# grbl_shield_hector.net
KiCad netlist of a schematic drawn in EAGLE
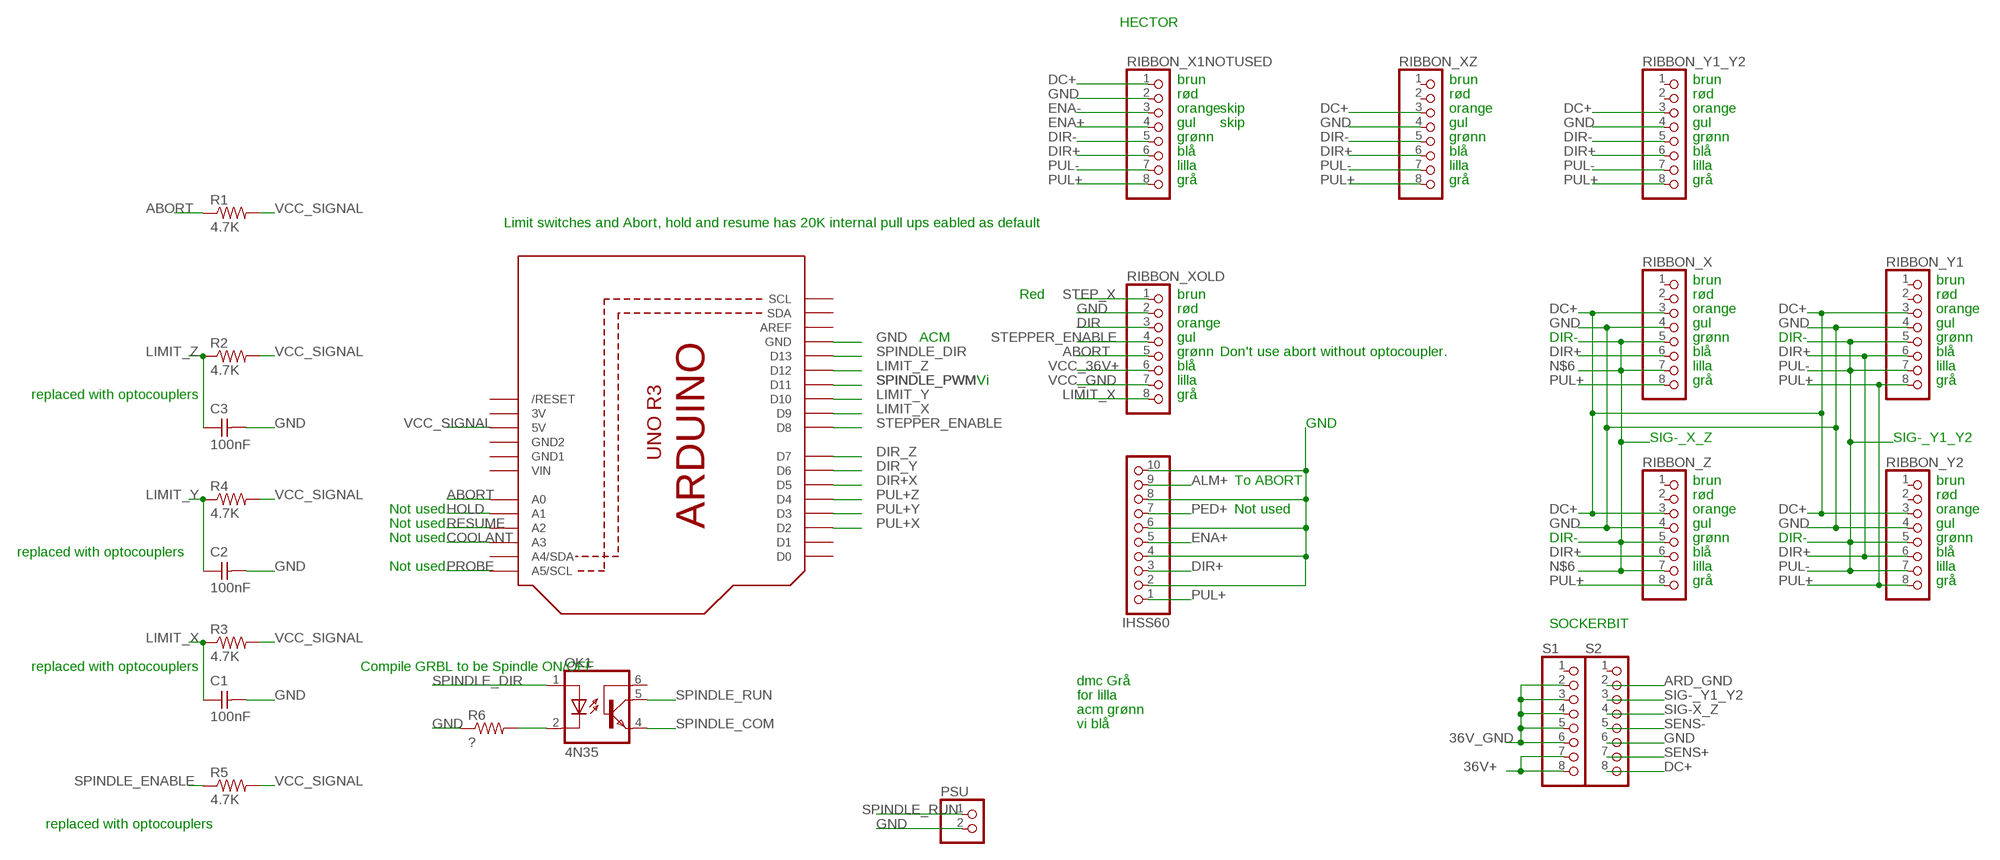
[diagram p0: schematic, sheet 1]

(export (version "E")
  (design (tool "Eeschema 10.0.6"))
  (components
    (comp (ref "C1")
      (value "100nF")
      (footprint "eagle-import:C1206FAB")
      (libsource (lib "eagle-import") (part "CAP-UNPOLARIZEDFAB"))
    )
    (comp (ref "C2")
      (value "100nF")
      (footprint "eagle-import:C1206FAB")
      (libsource (lib "eagle-import") (part "CAP-UNPOLARIZEDFAB"))
    )
    (comp (ref "C3")
      (value "100nF")
      (footprint "eagle-import:C1206FAB")
      (libsource (lib "eagle-import") (part "CAP-UNPOLARIZEDFAB"))
    )
    (comp (ref "IHSS60")
      (value "PINHD-1X10")
      (footprint "eagle-import:1X10")
      (libsource (lib "eagle-import") (part "PINHD-1X10"))
    )
    (comp (ref "OK1")
      (value "4N35")
      (footprint "eagle-import:DIL06")
      (libsource (lib "eagle-import") (part "4N35"))
    )
    (comp (ref "PSU")
      (value "PINHD-1X2")
      (footprint "eagle-import:1X02")
      (libsource (lib "eagle-import") (part "PINHD-1X2"))
    )
    (comp (ref "Q1")
      (value "ARDUINOR3-NOIOREF-NOTEXT")
      (footprint "eagle-import:ARDUINOR3-NOTEXT-NOIOREF")
      (libsource (lib "eagle-import") (part "ARDUINOR3-NOIOREF-NOTEXT"))
    )
    (comp (ref "R1")
      (value "4.7K")
      (footprint "eagle-import:R1206FAB")
      (libsource (lib "eagle-import") (part "RES-US1206FAB"))
    )
    (comp (ref "R2")
      (value "4.7K")
      (footprint "eagle-import:R1206FAB")
      (libsource (lib "eagle-import") (part "RES-US1206FAB"))
    )
    (comp (ref "R3")
      (value "4.7K")
      (footprint "eagle-import:R1206FAB")
      (libsource (lib "eagle-import") (part "RES-US1206FAB"))
    )
    (comp (ref "R4")
      (value "4.7K")
      (footprint "eagle-import:R1206FAB")
      (libsource (lib "eagle-import") (part "RES-US1206FAB"))
    )
    (comp (ref "R5")
      (value "4.7K")
      (footprint "eagle-import:R1206FAB")
      (libsource (lib "eagle-import") (part "RES-US1206FAB"))
    )
    (comp (ref "R6")
      (value "?")
      (footprint "eagle-import:R1206FAB")
      (libsource (lib "eagle-import") (part "RES-US1206FAB"))
    )
    (comp (ref "RIBBON_X")
      (value "PINHD-1X8")
      (footprint "eagle-import:1X08")
      (libsource (lib "eagle-import") (part "PINHD-1X8"))
    )
    (comp (ref "RIBBON_X1NOTUSED")
      (value "PINHD-1X8")
      (footprint "eagle-import:1X08")
      (libsource (lib "eagle-import") (part "PINHD-1X8"))
    )
    (comp (ref "RIBBON_XOLD")
      (value "PINHD-1X8")
      (footprint "eagle-import:1X08")
      (libsource (lib "eagle-import") (part "PINHD-1X8"))
    )
    (comp (ref "RIBBON_XZ")
      (value "PINHD-1X8")
      (footprint "eagle-import:1X08")
      (libsource (lib "eagle-import") (part "PINHD-1X8"))
    )
    (comp (ref "RIBBON_Y1")
      (value "PINHD-1X8")
      (footprint "eagle-import:1X08")
      (libsource (lib "eagle-import") (part "PINHD-1X8"))
    )
    (comp (ref "RIBBON_Y1_Y2")
      (value "PINHD-1X8")
      (footprint "eagle-import:1X08")
      (libsource (lib "eagle-import") (part "PINHD-1X8"))
    )
    (comp (ref "RIBBON_Y2")
      (value "PINHD-1X8")
      (footprint "eagle-import:1X08")
      (libsource (lib "eagle-import") (part "PINHD-1X8"))
    )
    (comp (ref "RIBBON_Z")
      (value "PINHD-1X8")
      (footprint "eagle-import:1X08")
      (libsource (lib "eagle-import") (part "PINHD-1X8"))
    )
    (comp (ref "S1")
      (value "PINHD-1X8")
      (footprint "eagle-import:1X08")
      (libsource (lib "eagle-import") (part "PINHD-1X8"))
    )
    (comp (ref "S2")
      (value "PINHD-1X8")
      (footprint "eagle-import:1X08")
      (libsource (lib "eagle-import") (part "PINHD-1X8"))
    )
  )
  (nets
    (net (code "1") (name "/3V") (class "Default")
      (node (ref "Q1") (pin "3V") (pinfunction "3V_3V") (pintype "power_in"))
    )
    (net (code "2") (name "/36V+") (class "Default")
      (node (ref "S1") (pin "7") (pinfunction "7_7") (pintype "passive"))
      (node (ref "S1") (pin "8") (pinfunction "8_8") (pintype "passive"))
    )
    (net (code "3") (name "/36V_GND") (class "Default")
      (node (ref "S1") (pin "2") (pinfunction "2_2") (pintype "passive"))
      (node (ref "S1") (pin "3") (pinfunction "3_3") (pintype "passive"))
      (node (ref "S1") (pin "4") (pinfunction "4_4") (pintype "passive"))
      (node (ref "S1") (pin "5") (pinfunction "5_5") (pintype "passive"))
      (node (ref "S1") (pin "6") (pinfunction "6_6") (pintype "passive"))
    )
    (net (code "4") (name "/ABORT") (class "Default")
      (node (ref "Q1") (pin "A0") (pinfunction "A0_A0") (pintype "bidirectional"))
      (node (ref "R1") (pin "1") (pinfunction "1_1") (pintype "passive"))
      (node (ref "RIBBON_XOLD") (pin "5") (pinfunction "5_5") (pintype "passive"))
    )
    (net (code "5") (name "/ALM+") (class "Default")
      (node (ref "IHSS60") (pin "9") (pinfunction "9_9") (pintype "passive"))
    )
    (net (code "6") (name "/ARD_GND") (class "Default")
      (node (ref "S2") (pin "2") (pinfunction "2_2") (pintype "passive"))
    )
    (net (code "7") (name "/COOLANT") (class "Default")
      (node (ref "Q1") (pin "A3") (pinfunction "A3_A3") (pintype "bidirectional"))
    )
    (net (code "8") (name "/DC+") (class "Default")
      (node (ref "RIBBON_X") (pin "3") (pinfunction "3_3") (pintype "passive"))
      (node (ref "RIBBON_X1NOTUSED") (pin "1") (pinfunction "1_1") (pintype "passive"))
      (node (ref "RIBBON_XZ") (pin "3") (pinfunction "3_3") (pintype "passive"))
      (node (ref "RIBBON_Y1") (pin "3") (pinfunction "3_3") (pintype "passive"))
      (node (ref "RIBBON_Y1_Y2") (pin "3") (pinfunction "3_3") (pintype "passive"))
      (node (ref "RIBBON_Y2") (pin "3") (pinfunction "3_3") (pintype "passive"))
      (node (ref "RIBBON_Z") (pin "3") (pinfunction "3_3") (pintype "passive"))
      (node (ref "S2") (pin "8") (pinfunction "8_8") (pintype "passive"))
    )
    (net (code "9") (name "/DIR") (class "Default")
      (node (ref "RIBBON_XOLD") (pin "3") (pinfunction "3_3") (pintype "passive"))
    )
    (net (code "10") (name "/DIR+") (class "Default")
      (node (ref "IHSS60") (pin "3") (pinfunction "3_3") (pintype "passive"))
      (node (ref "RIBBON_X") (pin "6") (pinfunction "6_6") (pintype "passive"))
      (node (ref "RIBBON_X1NOTUSED") (pin "6") (pinfunction "6_6") (pintype "passive"))
      (node (ref "RIBBON_XZ") (pin "6") (pinfunction "6_6") (pintype "passive"))
      (node (ref "RIBBON_Y1") (pin "6") (pinfunction "6_6") (pintype "passive"))
      (node (ref "RIBBON_Y1_Y2") (pin "6") (pinfunction "6_6") (pintype "passive"))
      (node (ref "RIBBON_Y2") (pin "6") (pinfunction "6_6") (pintype "passive"))
      (node (ref "RIBBON_Z") (pin "6") (pinfunction "6_6") (pintype "passive"))
    )
    (net (code "11") (name "/DIR+X") (class "Default")
      (node (ref "Q1") (pin "D5") (pinfunction "D5_D5") (pintype "bidirectional"))
    )
    (net (code "12") (name "/DIR-") (class "Default")
      (node (ref "RIBBON_X1NOTUSED") (pin "5") (pinfunction "5_5") (pintype "passive"))
      (node (ref "RIBBON_XZ") (pin "5") (pinfunction "5_5") (pintype "passive"))
      (node (ref "RIBBON_Y1_Y2") (pin "5") (pinfunction "5_5") (pintype "passive"))
    )
    (net (code "13") (name "/DIR_Y") (class "Default")
      (node (ref "Q1") (pin "D6") (pinfunction "D6_D6") (pintype "bidirectional"))
    )
    (net (code "14") (name "/DIR_Z") (class "Default")
      (node (ref "Q1") (pin "D7") (pinfunction "D7_D7") (pintype "bidirectional"))
    )
    (net (code "15") (name "/ENA+") (class "Default")
      (node (ref "IHSS60") (pin "5") (pinfunction "5_5") (pintype "passive"))
      (node (ref "RIBBON_X1NOTUSED") (pin "4") (pinfunction "4_4") (pintype "passive"))
    )
    (net (code "16") (name "/ENA-") (class "Default")
      (node (ref "RIBBON_X1NOTUSED") (pin "3") (pinfunction "3_3") (pintype "passive"))
    )
    (net (code "17") (name "/GND") (class "Default")
      (node (ref "C1") (pin "2") (pinfunction "2_2") (pintype "passive"))
      (node (ref "C2") (pin "2") (pinfunction "2_2") (pintype "passive"))
      (node (ref "C3") (pin "2") (pinfunction "2_2") (pintype "passive"))
      (node (ref "PSU") (pin "2") (pinfunction "2_2") (pintype "passive"))
      (node (ref "Q1") (pin "GND") (pinfunction "GND_GND") (pintype "power_in"))
      (node (ref "R6") (pin "1") (pinfunction "1_1") (pintype "passive"))
      (node (ref "RIBBON_X") (pin "4") (pinfunction "4_4") (pintype "passive"))
      (node (ref "RIBBON_X1NOTUSED") (pin "2") (pinfunction "2_2") (pintype "passive"))
      (node (ref "RIBBON_XOLD") (pin "2") (pinfunction "2_2") (pintype "passive"))
      (node (ref "RIBBON_XZ") (pin "4") (pinfunction "4_4") (pintype "passive"))
      (node (ref "RIBBON_Y1") (pin "4") (pinfunction "4_4") (pintype "passive"))
      (node (ref "RIBBON_Y1_Y2") (pin "4") (pinfunction "4_4") (pintype "passive"))
      (node (ref "RIBBON_Y2") (pin "4") (pinfunction "4_4") (pintype "passive"))
      (node (ref "RIBBON_Z") (pin "4") (pinfunction "4_4") (pintype "passive"))
      (node (ref "S2") (pin "6") (pinfunction "6_6") (pintype "passive"))
    )
    (net (code "18") (name "/GND1") (class "Default")
      (node (ref "Q1") (pin "GND1") (pinfunction "GND1_GND1") (pintype "power_in"))
    )
    (net (code "19") (name "/GND2") (class "Default")
      (node (ref "Q1") (pin "GND2") (pinfunction "GND2_GND2") (pintype "power_in"))
    )
    (net (code "20") (name "/HOLD") (class "Default")
      (node (ref "Q1") (pin "A1") (pinfunction "A1_A1") (pintype "bidirectional"))
    )
    (net (code "21") (name "/LIMIT_X") (class "Default")
      (node (ref "C1") (pin "1") (pinfunction "1_1") (pintype "passive"))
      (node (ref "Q1") (pin "D9") (pinfunction "D9_D9") (pintype "bidirectional"))
      (node (ref "R3") (pin "1") (pinfunction "1_1") (pintype "passive"))
      (node (ref "RIBBON_XOLD") (pin "8") (pinfunction "8_8") (pintype "passive"))
    )
    (net (code "22") (name "/LIMIT_Y") (class "Default")
      (node (ref "C2") (pin "1") (pinfunction "1_1") (pintype "passive"))
      (node (ref "Q1") (pin "D10") (pinfunction "D10_D10") (pintype "bidirectional"))
      (node (ref "R4") (pin "1") (pinfunction "1_1") (pintype "passive"))
    )
    (net (code "23") (name "/LIMIT_Z") (class "Default")
      (node (ref "C3") (pin "1") (pinfunction "1_1") (pintype "passive"))
      (node (ref "Q1") (pin "D12") (pinfunction "D12_D12") (pintype "bidirectional"))
      (node (ref "R2") (pin "1") (pinfunction "1_1") (pintype "passive"))
    )
    (net (code "24") (name "/N$6") (class "Default")
      (node (ref "RIBBON_X") (pin "5") (pinfunction "5_5") (pintype "passive"))
      (node (ref "RIBBON_X") (pin "7") (pinfunction "7_7") (pintype "passive"))
      (node (ref "RIBBON_Z") (pin "5") (pinfunction "5_5") (pintype "passive"))
      (node (ref "RIBBON_Z") (pin "7") (pinfunction "7_7") (pintype "passive"))
    )
    (net (code "25") (name "/PED+") (class "Default")
      (node (ref "IHSS60") (pin "7") (pinfunction "7_7") (pintype "passive"))
    )
    (net (code "26") (name "/PROBE") (class "Default")
      (node (ref "Q1") (pin "A5") (pinfunction "A5/SCL_A5") (pintype "bidirectional"))
    )
    (net (code "27") (name "/PUL+") (class "Default")
      (node (ref "IHSS60") (pin "1") (pinfunction "1_1") (pintype "passive"))
      (node (ref "RIBBON_X") (pin "8") (pinfunction "8_8") (pintype "passive"))
      (node (ref "RIBBON_X1NOTUSED") (pin "8") (pinfunction "8_8") (pintype "passive"))
      (node (ref "RIBBON_XZ") (pin "8") (pinfunction "8_8") (pintype "passive"))
      (node (ref "RIBBON_Y1") (pin "8") (pinfunction "8_8") (pintype "passive"))
      (node (ref "RIBBON_Y1_Y2") (pin "8") (pinfunction "8_8") (pintype "passive"))
      (node (ref "RIBBON_Y2") (pin "8") (pinfunction "8_8") (pintype "passive"))
      (node (ref "RIBBON_Z") (pin "8") (pinfunction "8_8") (pintype "passive"))
    )
    (net (code "28") (name "/PUL+X") (class "Default")
      (node (ref "Q1") (pin "D2") (pinfunction "D2_D2") (pintype "bidirectional"))
    )
    (net (code "29") (name "/PUL+Y") (class "Default")
      (node (ref "Q1") (pin "D3") (pinfunction "D3_D3") (pintype "bidirectional"))
    )
    (net (code "30") (name "/PUL+Z") (class "Default")
      (node (ref "Q1") (pin "D4") (pinfunction "D4_D4") (pintype "bidirectional"))
    )
    (net (code "31") (name "/PUL-") (class "Default")
      (node (ref "RIBBON_X1NOTUSED") (pin "7") (pinfunction "7_7") (pintype "passive"))
      (node (ref "RIBBON_XZ") (pin "7") (pinfunction "7_7") (pintype "passive"))
      (node (ref "RIBBON_Y1") (pin "5") (pinfunction "5_5") (pintype "passive"))
      (node (ref "RIBBON_Y1") (pin "7") (pinfunction "7_7") (pintype "passive"))
      (node (ref "RIBBON_Y1_Y2") (pin "7") (pinfunction "7_7") (pintype "passive"))
      (node (ref "RIBBON_Y2") (pin "5") (pinfunction "5_5") (pintype "passive"))
      (node (ref "RIBBON_Y2") (pin "7") (pinfunction "7_7") (pintype "passive"))
    )
    (net (code "32") (name "/RESUME") (class "Default")
      (node (ref "Q1") (pin "A2") (pinfunction "A2_A2") (pintype "bidirectional"))
    )
    (net (code "33") (name "/SENS+") (class "Default")
      (node (ref "S2") (pin "7") (pinfunction "7_7") (pintype "passive"))
    )
    (net (code "34") (name "/SENS-") (class "Default")
      (node (ref "S2") (pin "5") (pinfunction "5_5") (pintype "passive"))
    )
    (net (code "35") (name "/SIG-X_Z") (class "Default")
      (node (ref "S2") (pin "4") (pinfunction "4_4") (pintype "passive"))
    )
    (net (code "36") (name "/SIG-_Y1_Y2") (class "Default")
      (node (ref "S2") (pin "3") (pinfunction "3_3") (pintype "passive"))
    )
    (net (code "37") (name "/SPINDLE_COM") (class "Default")
      (node (ref "OK1") (pin "4") (pinfunction "EMI_4") (pintype "passive"))
    )
    (net (code "38") (name "/SPINDLE_DIR") (class "Default")
      (node (ref "OK1") (pin "1") (pinfunction "A_1") (pintype "passive"))
      (node (ref "Q1") (pin "D13") (pinfunction "D13_D13") (pintype "bidirectional"))
    )
    (net (code "39") (name "/SPINDLE_ENABLE") (class "Default")
      (node (ref "R5") (pin "1") (pinfunction "1_1") (pintype "passive"))
    )
    (net (code "40") (name "/SPINDLE_PWM") (class "Default")
      (node (ref "Q1") (pin "D11") (pinfunction "D11_D11") (pintype "bidirectional"))
    )
    (net (code "41") (name "/SPINDLE_RUN") (class "Default")
      (node (ref "OK1") (pin "5") (pinfunction "COL_5") (pintype "passive"))
      (node (ref "PSU") (pin "1") (pinfunction "1_1") (pintype "passive"))
    )
    (net (code "42") (name "/STEPPER_ENABLE") (class "Default")
      (node (ref "Q1") (pin "D8") (pinfunction "D8_D8") (pintype "bidirectional"))
      (node (ref "RIBBON_XOLD") (pin "4") (pinfunction "4_4") (pintype "passive"))
    )
    (net (code "43") (name "/STEP_X") (class "Default")
      (node (ref "RIBBON_XOLD") (pin "1") (pinfunction "1_1") (pintype "passive"))
    )
    (net (code "44") (name "/VCC_36V+") (class "Default")
      (node (ref "RIBBON_XOLD") (pin "6") (pinfunction "6_6") (pintype "passive"))
    )
    (net (code "45") (name "/VCC_GND") (class "Default")
      (node (ref "RIBBON_XOLD") (pin "7") (pinfunction "7_7") (pintype "passive"))
    )
    (net (code "46") (name "/VCC_SIGNAL") (class "Default")
      (node (ref "Q1") (pin "5V") (pinfunction "5V_5V") (pintype "power_in"))
      (node (ref "R1") (pin "2") (pinfunction "2_2") (pintype "passive"))
      (node (ref "R2") (pin "2") (pinfunction "2_2") (pintype "passive"))
      (node (ref "R3") (pin "2") (pinfunction "2_2") (pintype "passive"))
      (node (ref "R4") (pin "2") (pinfunction "2_2") (pintype "passive"))
      (node (ref "R5") (pin "2") (pinfunction "2_2") (pintype "passive"))
    )
    (net (code "47") (name "/VIN") (class "Default")
      (node (ref "Q1") (pin "VIN") (pinfunction "VIN_VIN") (pintype "power_in"))
    )
    (net (code "48") (name "Net-(IHSS60-Pad10)") (class "Default")
      (node (ref "IHSS60") (pin "10") (pinfunction "10_10") (pintype "passive"))
      (node (ref "IHSS60") (pin "2") (pinfunction "2_2") (pintype "passive"))
      (node (ref "IHSS60") (pin "4") (pinfunction "4_4") (pintype "passive"))
      (node (ref "IHSS60") (pin "6") (pinfunction "6_6") (pintype "passive"))
      (node (ref "IHSS60") (pin "8") (pinfunction "8_8") (pintype "passive"))
    )
    (net (code "49") (name "Net-(OK1-C)") (class "Default")
      (node (ref "OK1") (pin "2") (pinfunction "C_2") (pintype "passive"))
      (node (ref "R6") (pin "2") (pinfunction "2_2") (pintype "passive"))
    )
    (net (code "50") (name "unconnected-(OK1-BAS-Pad6)") (class "Default")
      (node (ref "OK1") (pin "6") (pinfunction "BAS_6") (pintype "passive"))
    )
    (net (code "51") (name "unconnected-(Q1-A4{slash}SDA-PadA4)") (class "Default")
      (node (ref "Q1") (pin "A4") (pinfunction "A4/SDA_A4") (pintype "bidirectional"))
    )
    (net (code "52") (name "unconnected-(Q1-PadAREF)") (class "Default")
      (node (ref "Q1") (pin "AREF") (pinfunction "AREF_AREF") (pintype "bidirectional"))
    )
    (net (code "53") (name "unconnected-(Q1-PadD0)") (class "Default")
      (node (ref "Q1") (pin "D0") (pinfunction "D0_D0") (pintype "bidirectional"))
    )
    (net (code "54") (name "unconnected-(Q1-PadD1)") (class "Default")
      (node (ref "Q1") (pin "D1") (pinfunction "D1_D1") (pintype "bidirectional"))
    )
    (net (code "55") (name "unconnected-(Q1-PadSCL)") (class "Default")
      (node (ref "Q1") (pin "SCL") (pinfunction "SCL_SCL") (pintype "bidirectional"))
    )
    (net (code "56") (name "unconnected-(Q1-PadSDA)") (class "Default")
      (node (ref "Q1") (pin "SDA") (pinfunction "SDA_SDA") (pintype "bidirectional"))
    )
    (net (code "57") (name "unconnected-(Q1-{slash}RESET-PadRESET)") (class "Default")
      (node (ref "Q1") (pin "RESET") (pinfunction "/RESET_RESET") (pintype "bidirectional"))
    )
    (net (code "58") (name "unconnected-(RIBBON_X-Pad1)") (class "Default")
      (node (ref "RIBBON_X") (pin "1") (pinfunction "1_1") (pintype "passive"))
    )
    (net (code "59") (name "unconnected-(RIBBON_X-Pad2)") (class "Default")
      (node (ref "RIBBON_X") (pin "2") (pinfunction "2_2") (pintype "passive"))
    )
    (net (code "60") (name "unconnected-(RIBBON_XZ-Pad1)") (class "Default")
      (node (ref "RIBBON_XZ") (pin "1") (pinfunction "1_1") (pintype "passive"))
    )
    (net (code "61") (name "unconnected-(RIBBON_XZ-Pad2)") (class "Default")
      (node (ref "RIBBON_XZ") (pin "2") (pinfunction "2_2") (pintype "passive"))
    )
    (net (code "62") (name "unconnected-(RIBBON_Y1-Pad1)") (class "Default")
      (node (ref "RIBBON_Y1") (pin "1") (pinfunction "1_1") (pintype "passive"))
    )
    (net (code "63") (name "unconnected-(RIBBON_Y1-Pad2)") (class "Default")
      (node (ref "RIBBON_Y1") (pin "2") (pinfunction "2_2") (pintype "passive"))
    )
    (net (code "64") (name "unconnected-(RIBBON_Y1_Y2-Pad1)") (class "Default")
      (node (ref "RIBBON_Y1_Y2") (pin "1") (pinfunction "1_1") (pintype "passive"))
    )
    (net (code "65") (name "unconnected-(RIBBON_Y1_Y2-Pad2)") (class "Default")
      (node (ref "RIBBON_Y1_Y2") (pin "2") (pinfunction "2_2") (pintype "passive"))
    )
    (net (code "66") (name "unconnected-(RIBBON_Y2-Pad1)") (class "Default")
      (node (ref "RIBBON_Y2") (pin "1") (pinfunction "1_1") (pintype "passive"))
    )
    (net (code "67") (name "unconnected-(RIBBON_Y2-Pad2)") (class "Default")
      (node (ref "RIBBON_Y2") (pin "2") (pinfunction "2_2") (pintype "passive"))
    )
    (net (code "68") (name "unconnected-(RIBBON_Z-Pad1)") (class "Default")
      (node (ref "RIBBON_Z") (pin "1") (pinfunction "1_1") (pintype "passive"))
    )
    (net (code "69") (name "unconnected-(RIBBON_Z-Pad2)") (class "Default")
      (node (ref "RIBBON_Z") (pin "2") (pinfunction "2_2") (pintype "passive"))
    )
    (net (code "70") (name "unconnected-(S1-Pad1)") (class "Default")
      (node (ref "S1") (pin "1") (pinfunction "1_1") (pintype "passive"))
    )
    (net (code "71") (name "unconnected-(S2-Pad1)") (class "Default")
      (node (ref "S2") (pin "1") (pinfunction "1_1") (pintype "passive"))
    )
  )
)
